# SD_card.net
KiCad netlist of a schematic drawn in Altium Designer
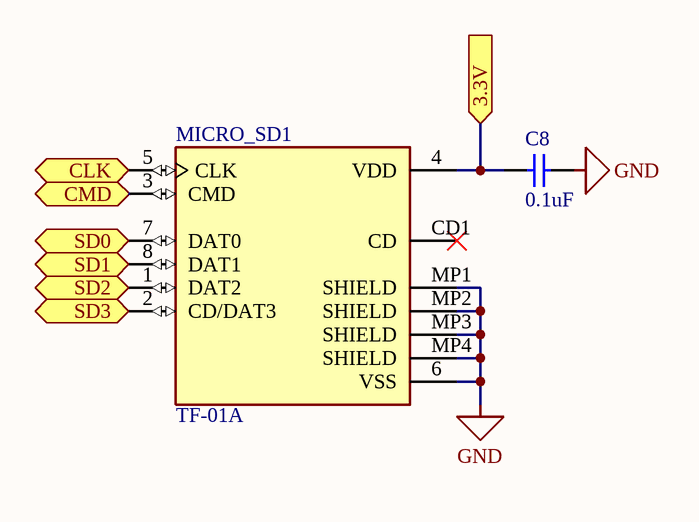
[diagram p0: SD card.SchDoc]

(export (version "E")
  (design (tool "Eeschema 10.0.6"))
  (components
    (comp (ref "C8")
      (value "0.1uF")
      (footprint "C 0805")
      (description "Capacitor non-pol")
      (libsource (lib "chipfc_libs") (part "Capacitor NP"))
    )
    (comp (ref "MICRO_SD1")
      (value "TF-01A")
      (footprint "TF-01A")
      (description "Standard Card Edge Connectors")
      (fields (field (name "MF") "HRO Electronics Co., Ltd."))
      (libsource (lib "TF-01A") (part "TF-01A"))
    )
  )
  (nets
    (net (code "1") (name "/3.3V") (class "Default")
      (node (ref "C8") (pin "1") (pinfunction "1_1") (pintype "passive"))
      (node (ref "MICRO_SD1") (pin "4") (pinfunction "VDD_4") (pintype "power_in"))
    )
    (net (code "2") (name "/CLK") (class "Default")
      (node (ref "MICRO_SD1") (pin "5") (pinfunction "CLK_5") (pintype "bidirectional"))
    )
    (net (code "3") (name "/CMD") (class "Default")
      (node (ref "MICRO_SD1") (pin "3") (pinfunction "CMD_3") (pintype "bidirectional"))
    )
    (net (code "4") (name "/SD0") (class "Default")
      (node (ref "MICRO_SD1") (pin "7") (pinfunction "DAT0_7") (pintype "bidirectional"))
    )
    (net (code "5") (name "/SD1") (class "Default")
      (node (ref "MICRO_SD1") (pin "8") (pinfunction "DAT1_8") (pintype "bidirectional"))
    )
    (net (code "6") (name "/SD2") (class "Default")
      (node (ref "MICRO_SD1") (pin "1") (pinfunction "DAT2_1") (pintype "bidirectional"))
    )
    (net (code "7") (name "/SD3") (class "Default")
      (node (ref "MICRO_SD1") (pin "2") (pinfunction "CD/DAT3_2") (pintype "bidirectional"))
    )
    (net (code "8") (name "GND") (class "Default")
      (node (ref "C8") (pin "2") (pinfunction "2_2") (pintype "passive"))
      (node (ref "MICRO_SD1") (pin "6") (pinfunction "VSS_6") (pintype "power_in"))
      (node (ref "MICRO_SD1") (pin "MP1") (pinfunction "SHIELD_MP1") (pintype "power_in"))
      (node (ref "MICRO_SD1") (pin "MP2") (pinfunction "SHIELD_MP2") (pintype "power_in"))
      (node (ref "MICRO_SD1") (pin "MP3") (pinfunction "SHIELD_MP3") (pintype "power_in"))
      (node (ref "MICRO_SD1") (pin "MP4") (pinfunction "SHIELD_MP4") (pintype "power_in"))
    )
    (net (code "9") (name "unconnected-(MICRO_SD1-CD-PadCD1)") (class "Default")
      (node (ref "MICRO_SD1") (pin "CD1") (pinfunction "CD_CD1") (pintype "passive+no_connect"))
    )
  )
)
